# RTC.net
KiCad netlist of a schematic drawn in Altium Designer
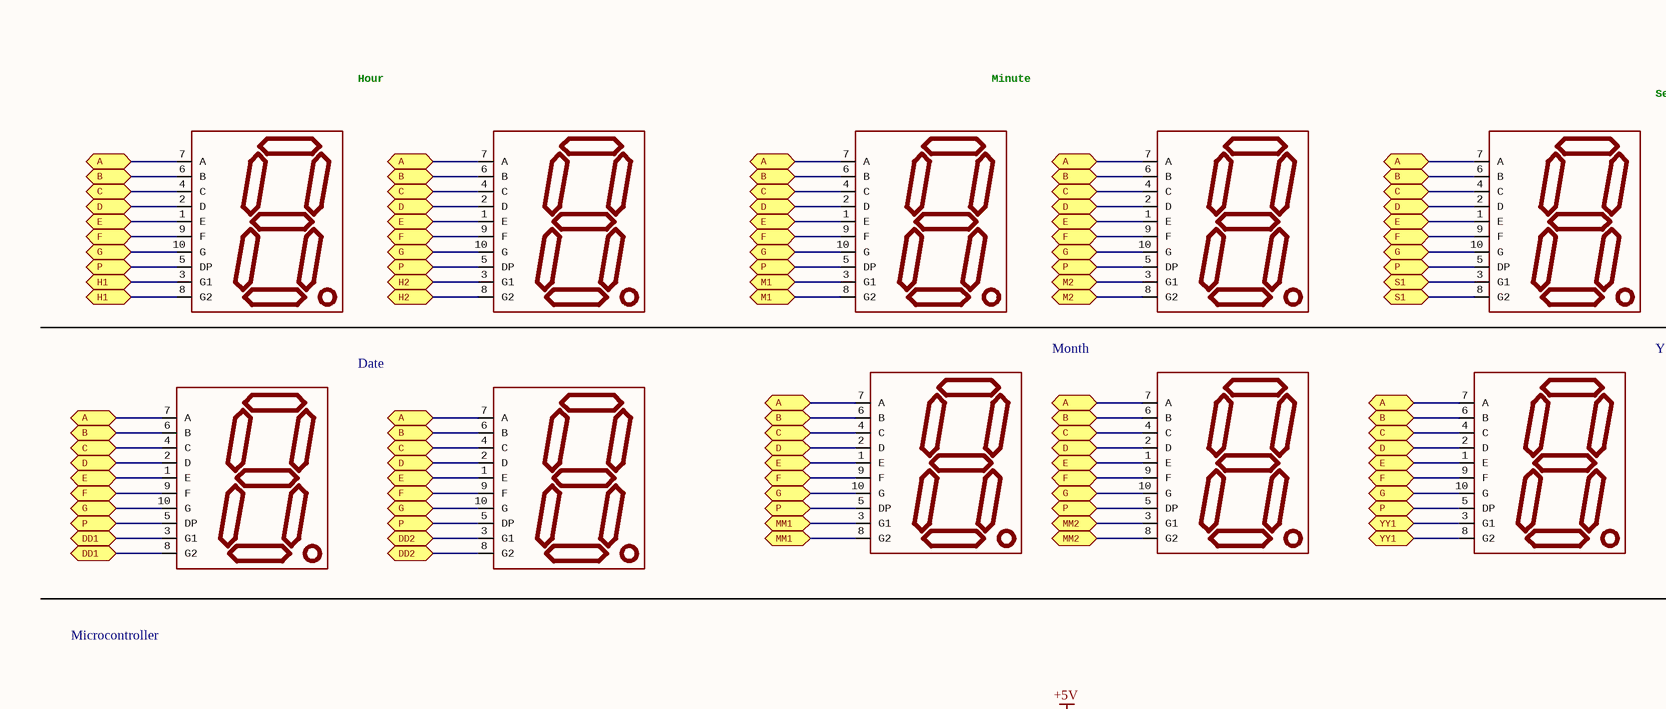
[diagram p0: RTC.SchDoc, top left]
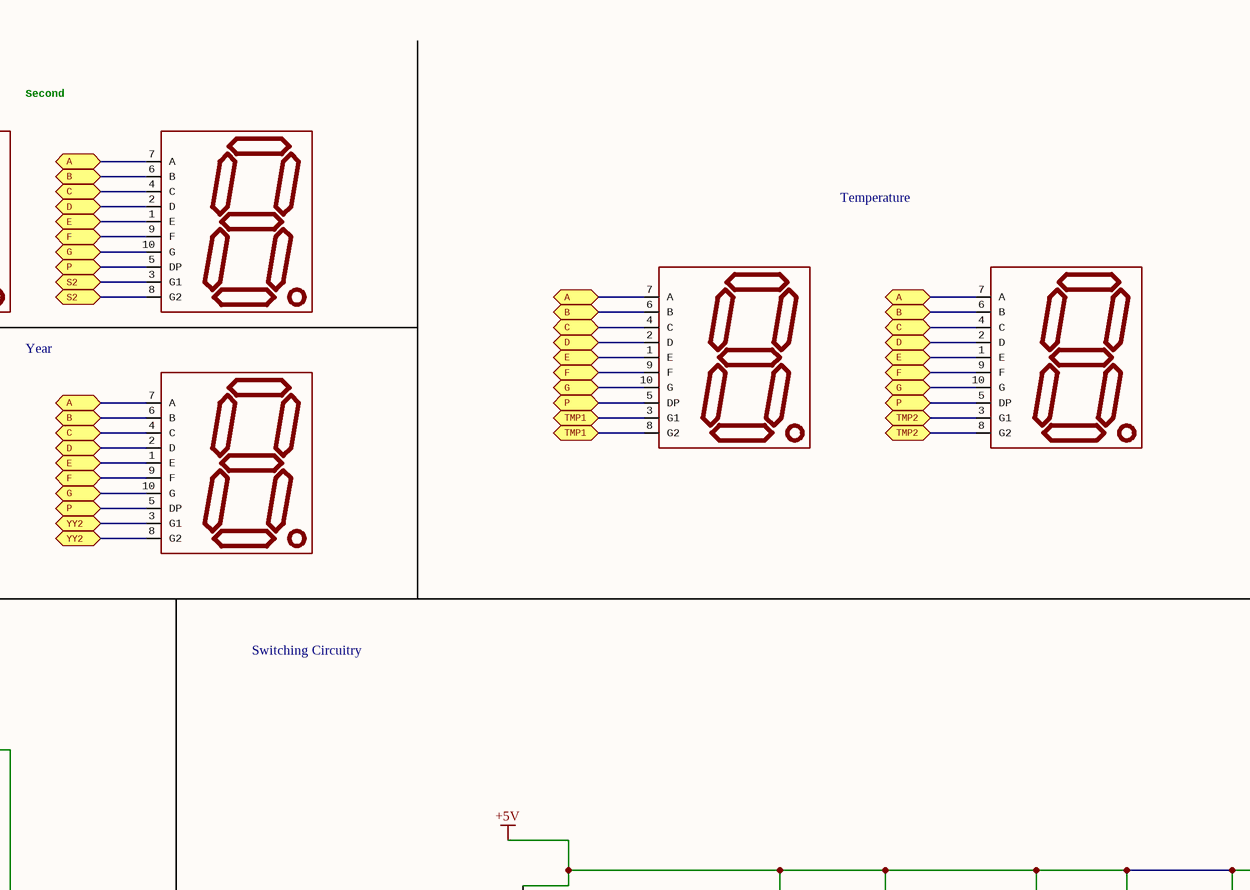
[diagram p1: RTC.SchDoc, top right]
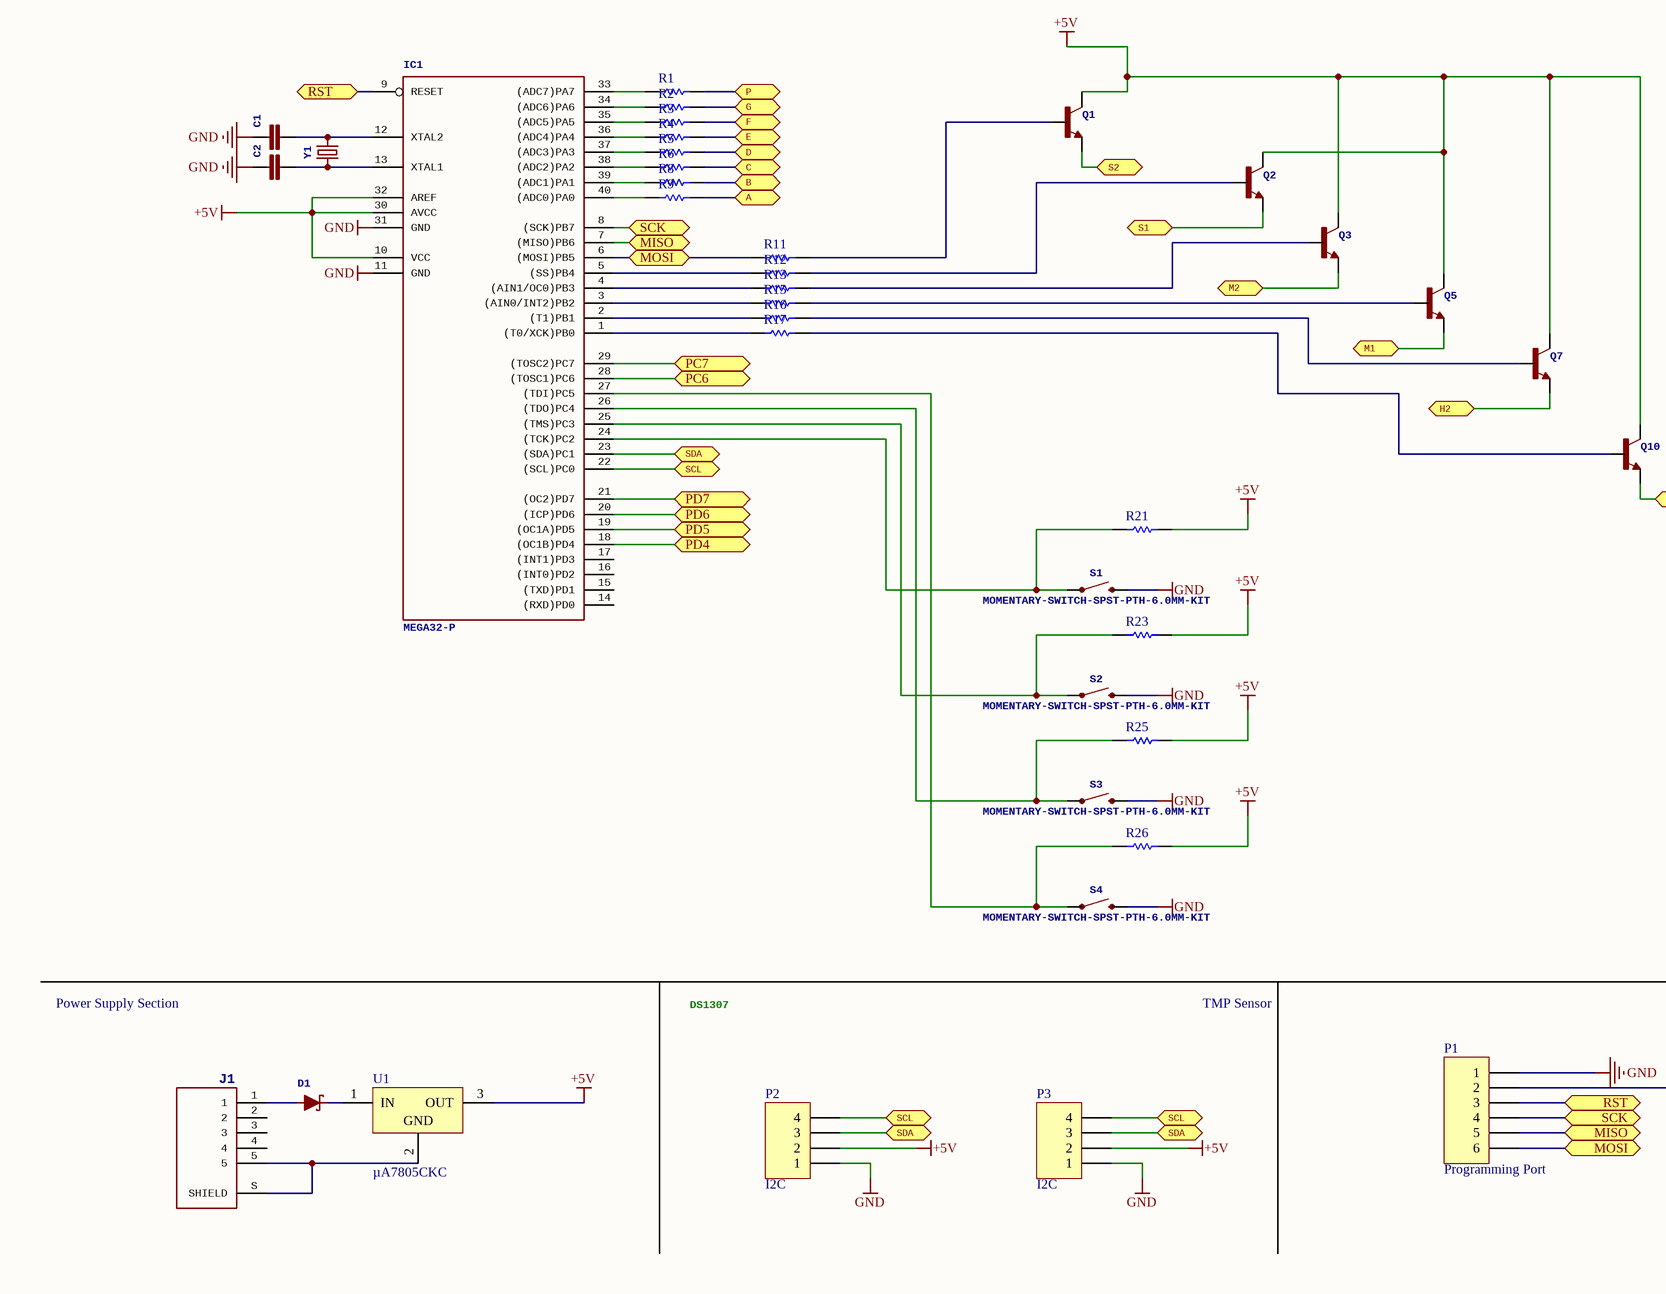
[diagram p2: RTC.SchDoc, bottom left]
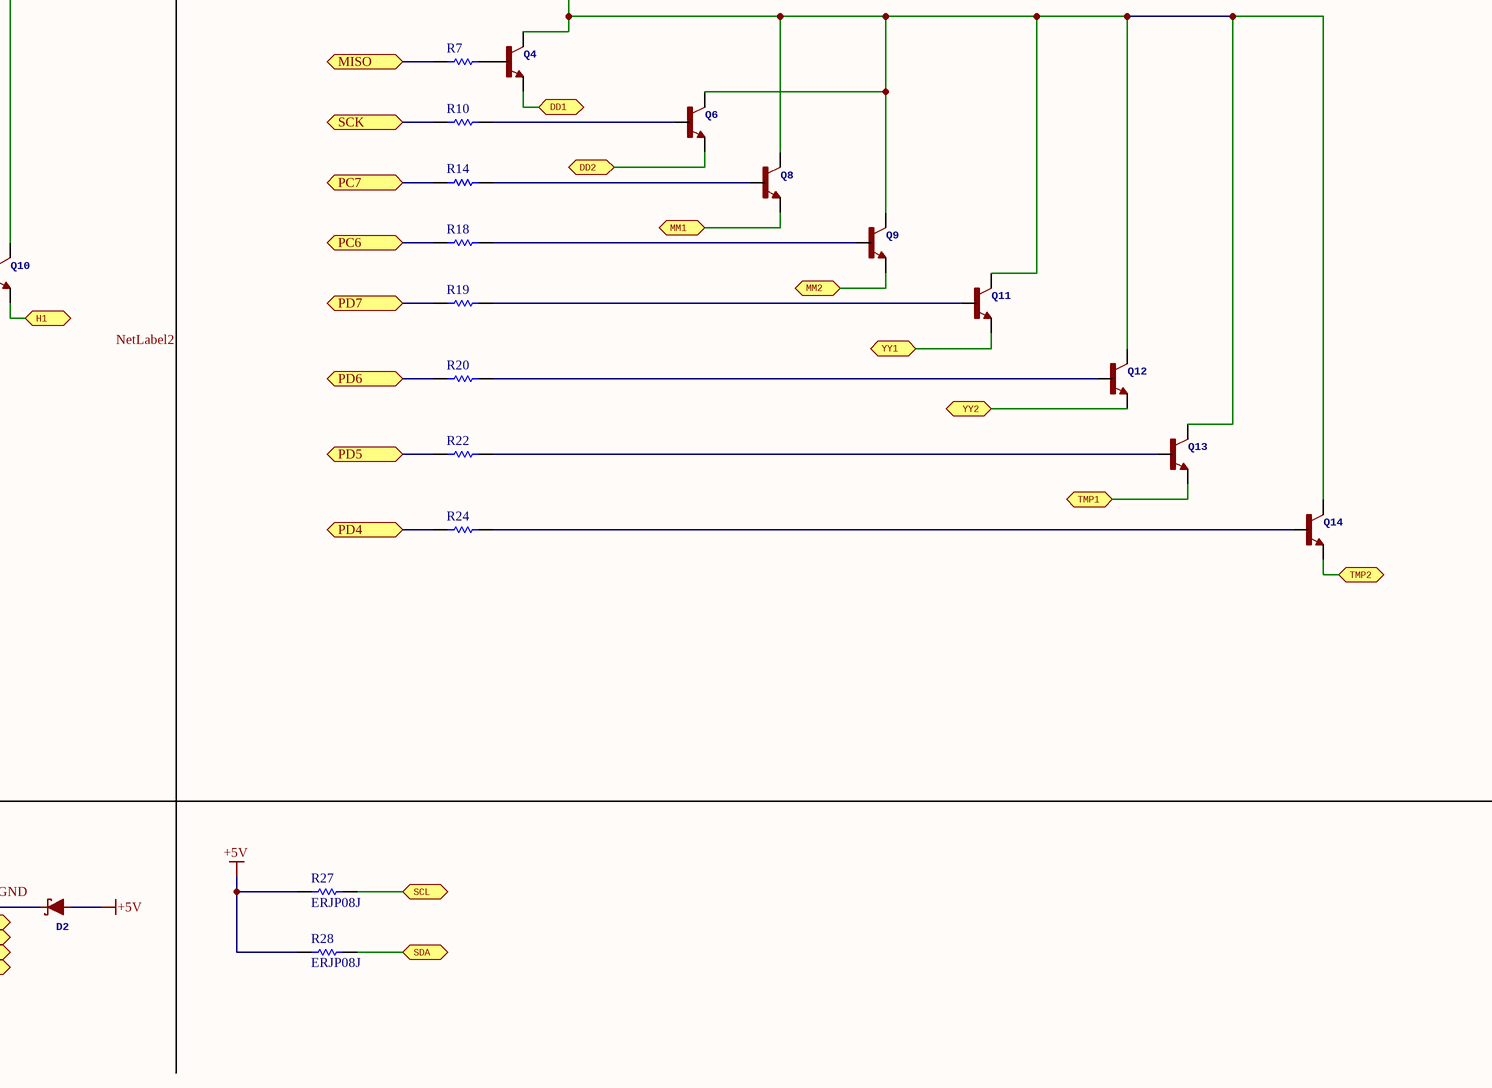
[diagram p3: RTC.SchDoc, bottom right]

(export (version "E")
  (design (tool "Eeschema 10.0.6"))
  (components
    (comp (ref "1")
      (value "7-SEGMENT-DISPLAYPTH")
      (footprint "7-SEGMENT-DISPLAY")
      (libsource (lib "SparkFun-Retired") (part "7-SEGMENT-DISPLAYPTH"))
    )
    (comp (ref "2")
      (value "7-SEGMENT-DISPLAYPTH")
      (footprint "7-SEGMENT-DISPLAY")
      (libsource (lib "SparkFun-Retired") (part "7-SEGMENT-DISPLAYPTH"))
    )
    (comp (ref "3")
      (value "7-SEGMENT-DISPLAYPTH")
      (footprint "7-SEGMENT-DISPLAY")
      (libsource (lib "SparkFun-Retired") (part "7-SEGMENT-DISPLAYPTH"))
    )
    (comp (ref "4")
      (value "7-SEGMENT-DISPLAYPTH")
      (footprint "7-SEGMENT-DISPLAY")
      (libsource (lib "SparkFun-Retired") (part "7-SEGMENT-DISPLAYPTH"))
    )
    (comp (ref "5")
      (value "7-SEGMENT-DISPLAYPTH")
      (footprint "7-SEGMENT-DISPLAY")
      (libsource (lib "SparkFun-Retired") (part "7-SEGMENT-DISPLAYPTH"))
    )
    (comp (ref "6")
      (value "7-SEGMENT-DISPLAYPTH")
      (footprint "7-SEGMENT-DISPLAY")
      (libsource (lib "SparkFun-Retired") (part "7-SEGMENT-DISPLAYPTH"))
    )
    (comp (ref "7")
      (value "7-SEGMENT-DISPLAYPTH")
      (footprint "7-SEGMENT-DISPLAY")
      (libsource (lib "SparkFun-Retired") (part "7-SEGMENT-DISPLAYPTH"))
    )
    (comp (ref "8")
      (value "7-SEGMENT-DISPLAYPTH")
      (footprint "7-SEGMENT-DISPLAY")
      (libsource (lib "SparkFun-Retired") (part "7-SEGMENT-DISPLAYPTH"))
    )
    (comp (ref "9")
      (value "7-SEGMENT-DISPLAYPTH")
      (footprint "7-SEGMENT-DISPLAY")
      (libsource (lib "SparkFun-Retired") (part "7-SEGMENT-DISPLAYPTH"))
    )
    (comp (ref "10")
      (value "7-SEGMENT-DISPLAYPTH")
      (footprint "7-SEGMENT-DISPLAY")
      (libsource (lib "SparkFun-Retired") (part "7-SEGMENT-DISPLAYPTH"))
    )
    (comp (ref "11")
      (value "7-SEGMENT-DISPLAYPTH")
      (footprint "7-SEGMENT-DISPLAY")
      (libsource (lib "SparkFun-Retired") (part "7-SEGMENT-DISPLAYPTH"))
    )
    (comp (ref "12")
      (value "7-SEGMENT-DISPLAYPTH")
      (footprint "7-SEGMENT-DISPLAY")
      (libsource (lib "SparkFun-Retired") (part "7-SEGMENT-DISPLAYPTH"))
    )
    (comp (ref "13")
      (value "7-SEGMENT-DISPLAYPTH")
      (footprint "7-SEGMENT-DISPLAY")
      (libsource (lib "SparkFun-Retired") (part "7-SEGMENT-DISPLAYPTH"))
    )
    (comp (ref "14")
      (value "7-SEGMENT-DISPLAYPTH")
      (footprint "7-SEGMENT-DISPLAY")
      (libsource (lib "SparkFun-Retired") (part "7-SEGMENT-DISPLAYPTH"))
    )
    (comp (ref "C1")
      (value "22PF-PTH-2.54MM-200V-5%")
      (footprint "CAP-PTH-2.54")
      (libsource (lib "SparkFun-Capacitors") (part "22PF-PTH-2.54MM-200V-5%"))
    )
    (comp (ref "C2")
      (value "22PF-PTH-2.54MM-200V-5%")
      (footprint "CAP-PTH-2.54")
      (libsource (lib "SparkFun-Capacitors") (part "22PF-PTH-2.54MM-200V-5%"))
    )
    (comp (ref "D1")
      (value "Schottky diode    A Schottky diode is a semiconductor diode which has a low forward voltage drop and a very fast switching action.")
      (footprint "SMA-DIODE")
      (libsource (lib "SparkFun-DiscreteSemi") (part "DIODE-SCHOTTKY-SS14"))
    )
    (comp (ref "D2")
      (value "Schottky diode    A Schottky diode is a semiconductor diode which has a low forward voltage drop and a very fast switching action.")
      (footprint "SMA-DIODE")
      (libsource (lib "SparkFun-DiscreteSemi") (part "DIODE-SCHOTTKY-SS14"))
    )
    (comp (ref "IC1")
      (value "MEGA32-P")
      (footprint "40P6")
      (fields (field (name "MPN") "ATMEGA32-16PU"))
      (libsource (lib "atmel") (part "MEGA32-P"))
    )
    (comp (ref "J1")
      (value "SMD+DIP Micro USB; MICRO-B-SMD")
      (footprint "HRS_ZX62D-B-5P8")
      (fields (field (name "MP") "ZX62D-B-5P8") (field (name "MF") "Hirose"))
      (libsource (lib "MicroUSB") (part "ZX62D-B-5P8"))
    )
    (comp (ref "P1")
      (value "Programming Port")
      (footprint "HDR1X6")
      (description "Header, 6-Pin")
      (fields (field (name "PUBLISHER") "Altium Limited"))
      (libsource (lib "Miscellaneous Connectors") (part "Header 6"))
    )
    (comp (ref "P2")
      (value "I2C")
      (footprint "HDR1X4")
      (description "Header, 4-Pin")
      (fields (field (name "PUBLISHER") "Altium Limited"))
      (libsource (lib "Miscellaneous Connectors") (part "Header 4"))
    )
    (comp (ref "P3")
      (value "I2C")
      (footprint "HDR1X4")
      (description "Header, 4-Pin")
      (fields (field (name "PUBLISHER") "Altium Limited"))
      (libsource (lib "Miscellaneous Connectors") (part "Header 4"))
    )
    (comp (ref "Q1")
      (value "NPN transistor    Current controlled devices typically used to amplify current or used as a switch.         BC547 -     COM-08928    (TO-92 45V 100mA) (1.Collector 2.Base 3.Emitter)             2N3904 -     COM-00521    (TO-92 40V 200mA) (1.Emitter 2.Base 3.Collector)             P2N2222A -     COM-12852    (TO-92 40V 600mA) (1.Collector 2.Base 3.Emitter)")
      (footprint "SOT23-3")
      (libsource (lib "SparkFun-DiscreteSemi") (part "TRANS_NPN-MMBT2222AL"))
    )
    (comp (ref "Q2")
      (value "NPN transistor    Current controlled devices typically used to amplify current or used as a switch.         BC547 -     COM-08928    (TO-92 45V 100mA) (1.Collector 2.Base 3.Emitter)             2N3904 -     COM-00521    (TO-92 40V 200mA) (1.Emitter 2.Base 3.Collector)             P2N2222A -     COM-12852    (TO-92 40V 600mA) (1.Collector 2.Base 3.Emitter)")
      (footprint "SOT23-3")
      (libsource (lib "SparkFun-DiscreteSemi") (part "TRANS_NPN-MMBT2222AL"))
    )
    (comp (ref "Q3")
      (value "NPN transistor    Current controlled devices typically used to amplify current or used as a switch.         BC547 -     COM-08928    (TO-92 45V 100mA) (1.Collector 2.Base 3.Emitter)             2N3904 -     COM-00521    (TO-92 40V 200mA) (1.Emitter 2.Base 3.Collector)             P2N2222A -     COM-12852    (TO-92 40V 600mA) (1.Collector 2.Base 3.Emitter)")
      (footprint "SOT23-3")
      (libsource (lib "SparkFun-DiscreteSemi") (part "TRANS_NPN-MMBT2222AL"))
    )
    (comp (ref "Q4")
      (value "NPN transistor    Current controlled devices typically used to amplify current or used as a switch.         BC547 -     COM-08928    (TO-92 45V 100mA) (1.Collector 2.Base 3.Emitter)             2N3904 -     COM-00521    (TO-92 40V 200mA) (1.Emitter 2.Base 3.Collector)             P2N2222A -     COM-12852    (TO-92 40V 600mA) (1.Collector 2.Base 3.Emitter)")
      (footprint "SOT23-3")
      (libsource (lib "SparkFun-DiscreteSemi") (part "TRANS_NPN-MMBT2222AL"))
    )
    (comp (ref "Q5")
      (value "NPN transistor    Current controlled devices typically used to amplify current or used as a switch.         BC547 -     COM-08928    (TO-92 45V 100mA) (1.Collector 2.Base 3.Emitter)             2N3904 -     COM-00521    (TO-92 40V 200mA) (1.Emitter 2.Base 3.Collector)             P2N2222A -     COM-12852    (TO-92 40V 600mA) (1.Collector 2.Base 3.Emitter)")
      (footprint "SOT23-3")
      (libsource (lib "SparkFun-DiscreteSemi") (part "TRANS_NPN-MMBT2222AL"))
    )
    (comp (ref "Q6")
      (value "NPN transistor    Current controlled devices typically used to amplify current or used as a switch.         BC547 -     COM-08928    (TO-92 45V 100mA) (1.Collector 2.Base 3.Emitter)             2N3904 -     COM-00521    (TO-92 40V 200mA) (1.Emitter 2.Base 3.Collector)             P2N2222A -     COM-12852    (TO-92 40V 600mA) (1.Collector 2.Base 3.Emitter)")
      (footprint "SOT23-3")
      (libsource (lib "SparkFun-DiscreteSemi") (part "TRANS_NPN-MMBT2222AL"))
    )
    (comp (ref "Q7")
      (value "NPN transistor    Current controlled devices typically used to amplify current or used as a switch.         BC547 -     COM-08928    (TO-92 45V 100mA) (1.Collector 2.Base 3.Emitter)             2N3904 -     COM-00521    (TO-92 40V 200mA) (1.Emitter 2.Base 3.Collector)             P2N2222A -     COM-12852    (TO-92 40V 600mA) (1.Collector 2.Base 3.Emitter)")
      (footprint "SOT23-3")
      (libsource (lib "SparkFun-DiscreteSemi") (part "TRANS_NPN-MMBT2222AL"))
    )
    (comp (ref "Q8")
      (value "NPN transistor    Current controlled devices typically used to amplify current or used as a switch.         BC547 -     COM-08928    (TO-92 45V 100mA) (1.Collector 2.Base 3.Emitter)             2N3904 -     COM-00521    (TO-92 40V 200mA) (1.Emitter 2.Base 3.Collector)             P2N2222A -     COM-12852    (TO-92 40V 600mA) (1.Collector 2.Base 3.Emitter)")
      (footprint "SOT23-3")
      (libsource (lib "SparkFun-DiscreteSemi") (part "TRANS_NPN-MMBT2222AL"))
    )
    (comp (ref "Q9")
      (value "NPN transistor    Current controlled devices typically used to amplify current or used as a switch.         BC547 -     COM-08928    (TO-92 45V 100mA) (1.Collector 2.Base 3.Emitter)             2N3904 -     COM-00521    (TO-92 40V 200mA) (1.Emitter 2.Base 3.Collector)             P2N2222A -     COM-12852    (TO-92 40V 600mA) (1.Collector 2.Base 3.Emitter)")
      (footprint "SOT23-3")
      (libsource (lib "SparkFun-DiscreteSemi") (part "TRANS_NPN-MMBT2222AL"))
    )
    (comp (ref "Q10")
      (value "NPN transistor    Current controlled devices typically used to amplify current or used as a switch.         BC547 -     COM-08928    (TO-92 45V 100mA) (1.Collector 2.Base 3.Emitter)             2N3904 -     COM-00521    (TO-92 40V 200mA) (1.Emitter 2.Base 3.Collector)             P2N2222A -     COM-12852    (TO-92 40V 600mA) (1.Collector 2.Base 3.Emitter)")
      (footprint "SOT23-3")
      (libsource (lib "SparkFun-DiscreteSemi") (part "TRANS_NPN-MMBT2222AL"))
    )
    (comp (ref "Q11")
      (value "NPN transistor    Current controlled devices typically used to amplify current or used as a switch.         BC547 -     COM-08928    (TO-92 45V 100mA) (1.Collector 2.Base 3.Emitter)             2N3904 -     COM-00521    (TO-92 40V 200mA) (1.Emitter 2.Base 3.Collector)             P2N2222A -     COM-12852    (TO-92 40V 600mA) (1.Collector 2.Base 3.Emitter)")
      (footprint "SOT23-3")
      (libsource (lib "SparkFun-DiscreteSemi") (part "TRANS_NPN-MMBT2222AL"))
    )
    (comp (ref "Q12")
      (value "NPN transistor    Current controlled devices typically used to amplify current or used as a switch.         BC547 -     COM-08928    (TO-92 45V 100mA) (1.Collector 2.Base 3.Emitter)             2N3904 -     COM-00521    (TO-92 40V 200mA) (1.Emitter 2.Base 3.Collector)             P2N2222A -     COM-12852    (TO-92 40V 600mA) (1.Collector 2.Base 3.Emitter)")
      (footprint "SOT23-3")
      (libsource (lib "SparkFun-DiscreteSemi") (part "TRANS_NPN-MMBT2222AL"))
    )
    (comp (ref "Q13")
      (value "NPN transistor    Current controlled devices typically used to amplify current or used as a switch.         BC547 -     COM-08928    (TO-92 45V 100mA) (1.Collector 2.Base 3.Emitter)             2N3904 -     COM-00521    (TO-92 40V 200mA) (1.Emitter 2.Base 3.Collector)             P2N2222A -     COM-12852    (TO-92 40V 600mA) (1.Collector 2.Base 3.Emitter)")
      (footprint "SOT23-3")
      (libsource (lib "SparkFun-DiscreteSemi") (part "TRANS_NPN-MMBT2222AL"))
    )
    (comp (ref "Q14")
      (value "NPN transistor    Current controlled devices typically used to amplify current or used as a switch.         BC547 -     COM-08928    (TO-92 45V 100mA) (1.Collector 2.Base 3.Emitter)             2N3904 -     COM-00521    (TO-92 40V 200mA) (1.Emitter 2.Base 3.Collector)             P2N2222A -     COM-12852    (TO-92 40V 600mA) (1.Collector 2.Base 3.Emitter)")
      (footprint "SOT23-3")
      (libsource (lib "SparkFun-DiscreteSemi") (part "TRANS_NPN-MMBT2222AL"))
    )
    (comp (ref "R1")
      (value "~")
      (footprint "8-1206")
      (description "Anti-Surge Thick Film Chip Resistor, 10 Ohm to 1M Ohm Range, 5% Tolerance, 1206 Size, 0.25 W")
      (fields (field (name "PUBLISHER") "Altium Limited"))
      (libsource (lib "Panasonic Resistor") (part "ERJP08J"))
    )
    (comp (ref "R2")
      (value "~")
      (footprint "8-1206")
      (description "Anti-Surge Thick Film Chip Resistor, 10 Ohm to 1M Ohm Range, 5% Tolerance, 1206 Size, 0.25 W")
      (fields (field (name "PUBLISHER") "Altium Limited"))
      (libsource (lib "Panasonic Resistor") (part "ERJP08J"))
    )
    (comp (ref "R3")
      (value "~")
      (footprint "8-1206")
      (description "Anti-Surge Thick Film Chip Resistor, 10 Ohm to 1M Ohm Range, 5% Tolerance, 1206 Size, 0.25 W")
      (fields (field (name "PUBLISHER") "Altium Limited"))
      (libsource (lib "Panasonic Resistor") (part "ERJP08J"))
    )
    (comp (ref "R4")
      (value "~")
      (footprint "8-1206")
      (description "Anti-Surge Thick Film Chip Resistor, 10 Ohm to 1M Ohm Range, 5% Tolerance, 1206 Size, 0.25 W")
      (fields (field (name "PUBLISHER") "Altium Limited"))
      (libsource (lib "Panasonic Resistor") (part "ERJP08J"))
    )
    (comp (ref "R5")
      (value "~")
      (footprint "8-1206")
      (description "Anti-Surge Thick Film Chip Resistor, 10 Ohm to 1M Ohm Range, 5% Tolerance, 1206 Size, 0.25 W")
      (fields (field (name "PUBLISHER") "Altium Limited"))
      (libsource (lib "Panasonic Resistor") (part "ERJP08J"))
    )
    (comp (ref "R6")
      (value "~")
      (footprint "8-1206")
      (description "Anti-Surge Thick Film Chip Resistor, 10 Ohm to 1M Ohm Range, 5% Tolerance, 1206 Size, 0.25 W")
      (fields (field (name "PUBLISHER") "Altium Limited"))
      (libsource (lib "Panasonic Resistor") (part "ERJP08J"))
    )
    (comp (ref "R7")
      (value "~")
      (footprint "8-1206")
      (description "Anti-Surge Thick Film Chip Resistor, 10 Ohm to 1M Ohm Range, 5% Tolerance, 1206 Size, 0.25 W")
      (fields (field (name "PUBLISHER") "Altium Limited"))
      (libsource (lib "Panasonic Resistor") (part "ERJP08J"))
    )
    (comp (ref "R8")
      (value "~")
      (footprint "8-1206")
      (description "Anti-Surge Thick Film Chip Resistor, 10 Ohm to 1M Ohm Range, 5% Tolerance, 1206 Size, 0.25 W")
      (fields (field (name "PUBLISHER") "Altium Limited"))
      (libsource (lib "Panasonic Resistor") (part "ERJP08J"))
    )
    (comp (ref "R9")
      (value "~")
      (footprint "8-1206")
      (description "Anti-Surge Thick Film Chip Resistor, 10 Ohm to 1M Ohm Range, 5% Tolerance, 1206 Size, 0.25 W")
      (fields (field (name "PUBLISHER") "Altium Limited"))
      (libsource (lib "Panasonic Resistor") (part "ERJP08J"))
    )
    (comp (ref "R10")
      (value "~")
      (footprint "8-1206")
      (description "Anti-Surge Thick Film Chip Resistor, 10 Ohm to 1M Ohm Range, 5% Tolerance, 1206 Size, 0.25 W")
      (fields (field (name "PUBLISHER") "Altium Limited"))
      (libsource (lib "Panasonic Resistor") (part "ERJP08J"))
    )
    (comp (ref "R11")
      (value "~")
      (footprint "8-1206")
      (description "Anti-Surge Thick Film Chip Resistor, 10 Ohm to 1M Ohm Range, 5% Tolerance, 1206 Size, 0.25 W")
      (fields (field (name "PUBLISHER") "Altium Limited"))
      (libsource (lib "Panasonic Resistor") (part "ERJP08J"))
    )
    (comp (ref "R12")
      (value "~")
      (footprint "8-1206")
      (description "Anti-Surge Thick Film Chip Resistor, 10 Ohm to 1M Ohm Range, 5% Tolerance, 1206 Size, 0.25 W")
      (fields (field (name "PUBLISHER") "Altium Limited"))
      (libsource (lib "Panasonic Resistor") (part "ERJP08J"))
    )
    (comp (ref "R13")
      (value "~")
      (footprint "8-1206")
      (description "Anti-Surge Thick Film Chip Resistor, 10 Ohm to 1M Ohm Range, 5% Tolerance, 1206 Size, 0.25 W")
      (fields (field (name "PUBLISHER") "Altium Limited"))
      (libsource (lib "Panasonic Resistor") (part "ERJP08J"))
    )
    (comp (ref "R14")
      (value "~")
      (footprint "8-1206")
      (description "Anti-Surge Thick Film Chip Resistor, 10 Ohm to 1M Ohm Range, 5% Tolerance, 1206 Size, 0.25 W")
      (fields (field (name "PUBLISHER") "Altium Limited"))
      (libsource (lib "Panasonic Resistor") (part "ERJP08J"))
    )
    (comp (ref "R15")
      (value "~")
      (footprint "8-1206")
      (description "Anti-Surge Thick Film Chip Resistor, 10 Ohm to 1M Ohm Range, 5% Tolerance, 1206 Size, 0.25 W")
      (fields (field (name "PUBLISHER") "Altium Limited"))
      (libsource (lib "Panasonic Resistor") (part "ERJP08J"))
    )
    (comp (ref "R16")
      (value "~")
      (footprint "8-1206")
      (description "Anti-Surge Thick Film Chip Resistor, 10 Ohm to 1M Ohm Range, 5% Tolerance, 1206 Size, 0.25 W")
      (fields (field (name "PUBLISHER") "Altium Limited"))
      (libsource (lib "Panasonic Resistor") (part "ERJP08J"))
    )
    (comp (ref "R17")
      (value "~")
      (footprint "8-1206")
      (description "Anti-Surge Thick Film Chip Resistor, 10 Ohm to 1M Ohm Range, 5% Tolerance, 1206 Size, 0.25 W")
      (fields (field (name "PUBLISHER") "Altium Limited"))
      (libsource (lib "Panasonic Resistor") (part "ERJP08J"))
    )
    (comp (ref "R18")
      (value "~")
      (footprint "8-1206")
      (description "Anti-Surge Thick Film Chip Resistor, 10 Ohm to 1M Ohm Range, 5% Tolerance, 1206 Size, 0.25 W")
      (fields (field (name "PUBLISHER") "Altium Limited"))
      (libsource (lib "Panasonic Resistor") (part "ERJP08J"))
    )
    (comp (ref "R19")
      (value "~")
      (footprint "8-1206")
      (description "Anti-Surge Thick Film Chip Resistor, 10 Ohm to 1M Ohm Range, 5% Tolerance, 1206 Size, 0.25 W")
      (fields (field (name "PUBLISHER") "Altium Limited"))
      (libsource (lib "Panasonic Resistor") (part "ERJP08J"))
    )
    (comp (ref "R20")
      (value "~")
      (footprint "8-1206")
      (description "Anti-Surge Thick Film Chip Resistor, 10 Ohm to 1M Ohm Range, 5% Tolerance, 1206 Size, 0.25 W")
      (fields (field (name "PUBLISHER") "Altium Limited"))
      (libsource (lib "Panasonic Resistor") (part "ERJP08J"))
    )
    (comp (ref "R21")
      (value "~")
      (footprint "8-1206")
      (description "Anti-Surge Thick Film Chip Resistor, 10 Ohm to 1M Ohm Range, 5% Tolerance, 1206 Size, 0.25 W")
      (fields (field (name "PUBLISHER") "Altium Limited"))
      (libsource (lib "Panasonic Resistor") (part "ERJP08J"))
    )
    (comp (ref "R22")
      (value "~")
      (footprint "8-1206")
      (description "Anti-Surge Thick Film Chip Resistor, 10 Ohm to 1M Ohm Range, 5% Tolerance, 1206 Size, 0.25 W")
      (fields (field (name "PUBLISHER") "Altium Limited"))
      (libsource (lib "Panasonic Resistor") (part "ERJP08J"))
    )
    (comp (ref "R23")
      (value "~")
      (footprint "8-1206")
      (description "Anti-Surge Thick Film Chip Resistor, 10 Ohm to 1M Ohm Range, 5% Tolerance, 1206 Size, 0.25 W")
      (fields (field (name "PUBLISHER") "Altium Limited"))
      (libsource (lib "Panasonic Resistor") (part "ERJP08J"))
    )
    (comp (ref "R24")
      (value "~")
      (footprint "8-1206")
      (description "Anti-Surge Thick Film Chip Resistor, 10 Ohm to 1M Ohm Range, 5% Tolerance, 1206 Size, 0.25 W")
      (fields (field (name "PUBLISHER") "Altium Limited"))
      (libsource (lib "Panasonic Resistor") (part "ERJP08J"))
    )
    (comp (ref "R25")
      (value "~")
      (footprint "8-1206")
      (description "Anti-Surge Thick Film Chip Resistor, 10 Ohm to 1M Ohm Range, 5% Tolerance, 1206 Size, 0.25 W")
      (fields (field (name "PUBLISHER") "Altium Limited"))
      (libsource (lib "Panasonic Resistor") (part "ERJP08J"))
    )
    (comp (ref "R26")
      (value "~")
      (footprint "8-1206")
      (description "Anti-Surge Thick Film Chip Resistor, 10 Ohm to 1M Ohm Range, 5% Tolerance, 1206 Size, 0.25 W")
      (fields (field (name "PUBLISHER") "Altium Limited"))
      (libsource (lib "Panasonic Resistor") (part "ERJP08J"))
    )
    (comp (ref "R27")
      (value "ERJP08J")
      (footprint "8-1206")
      (description "Anti-Surge Thick Film Chip Resistor, 10 Ohm to 1M Ohm Range, 5% Tolerance, 1206 Size, 0.25 W")
      (fields (field (name "PUBLISHER") "Altium Limited"))
      (libsource (lib "Panasonic Resistor") (part "ERJP08J"))
    )
    (comp (ref "R28")
      (value "ERJP08J")
      (footprint "8-1206")
      (description "Anti-Surge Thick Film Chip Resistor, 10 Ohm to 1M Ohm Range, 5% Tolerance, 1206 Size, 0.25 W")
      (fields (field (name "PUBLISHER") "Altium Limited"))
      (libsource (lib "Panasonic Resistor") (part "ERJP08J"))
    )
    (comp (ref "S1")
      (value "MOMENTARY-SWITCH-SPST-PTH-6.0MM-KIT")
      (footprint "TACTILE_SWITCH_PTH_6.0MM_KIT")
      (libsource (lib "SparkFun-Switches") (part "MOMENTARY-SWITCH-SPST-PTH-6.0MM-KIT"))
    )
    (comp (ref "S2")
      (value "MOMENTARY-SWITCH-SPST-PTH-6.0MM-KIT")
      (footprint "TACTILE_SWITCH_PTH_6.0MM_KIT")
      (libsource (lib "SparkFun-Switches") (part "MOMENTARY-SWITCH-SPST-PTH-6.0MM-KIT"))
    )
    (comp (ref "S3")
      (value "MOMENTARY-SWITCH-SPST-PTH-6.0MM-KIT")
      (footprint "TACTILE_SWITCH_PTH_6.0MM_KIT")
      (libsource (lib "SparkFun-Switches") (part "MOMENTARY-SWITCH-SPST-PTH-6.0MM-KIT"))
    )
    (comp (ref "S4")
      (value "MOMENTARY-SWITCH-SPST-PTH-6.0MM-KIT")
      (footprint "TACTILE_SWITCH_PTH_6.0MM_KIT")
      (libsource (lib "SparkFun-Switches") (part "MOMENTARY-SWITCH-SPST-PTH-6.0MM-KIT"))
    )
    (comp (ref "U1")
      (value "µA7805CKC")
      (footprint "KC03")
      (description "Positive-Voltage Regulator")
      (fields (field (name "PUBLISHER") "Altium Limited"))
      (libsource (lib "TI Power Mgt Voltage Regulator") (part "µA7805CKC"))
    )
    (comp (ref "Y1")
      (value "CRYSTAL-16MHZPTH-HC49US")
      (footprint "HC49US")
      (libsource (lib "SparkFun-Clocks") (part "CRYSTAL-16MHZPTH-HC49US"))
    )
  )
  (nets
    (net (code "1") (name "+5V") (class "Default")
      (node (ref "D2") (pin "A") (pinfunction "A_A") (pintype "passive"))
      (node (ref "IC1") (pin "10") (pinfunction "VCC_10") (pintype "power_in"))
      (node (ref "IC1") (pin "30") (pinfunction "AVCC_30") (pintype "power_in"))
      (node (ref "IC1") (pin "32") (pinfunction "AREF_32") (pintype "passive"))
      (node (ref "P2") (pin "2") (pinfunction "2_2") (pintype "passive"))
      (node (ref "P3") (pin "2") (pinfunction "2_2") (pintype "passive"))
      (node (ref "Q1") (pin "3") (pinfunction "C_3") (pintype "passive"))
      (node (ref "Q10") (pin "3") (pinfunction "C_3") (pintype "passive"))
      (node (ref "Q11") (pin "3") (pinfunction "C_3") (pintype "passive"))
      (node (ref "Q12") (pin "3") (pinfunction "C_3") (pintype "passive"))
      (node (ref "Q13") (pin "3") (pinfunction "C_3") (pintype "passive"))
      (node (ref "Q14") (pin "3") (pinfunction "C_3") (pintype "passive"))
      (node (ref "Q2") (pin "3") (pinfunction "C_3") (pintype "passive"))
      (node (ref "Q3") (pin "3") (pinfunction "C_3") (pintype "passive"))
      (node (ref "Q4") (pin "3") (pinfunction "C_3") (pintype "passive"))
      (node (ref "Q5") (pin "3") (pinfunction "C_3") (pintype "passive"))
      (node (ref "Q6") (pin "3") (pinfunction "C_3") (pintype "passive"))
      (node (ref "Q7") (pin "3") (pinfunction "C_3") (pintype "passive"))
      (node (ref "Q8") (pin "3") (pinfunction "C_3") (pintype "passive"))
      (node (ref "Q9") (pin "3") (pinfunction "C_3") (pintype "passive"))
      (node (ref "R21") (pin "2") (pinfunction "2_2") (pintype "passive"))
      (node (ref "R23") (pin "2") (pinfunction "2_2") (pintype "passive"))
      (node (ref "R25") (pin "2") (pinfunction "2_2") (pintype "passive"))
      (node (ref "R26") (pin "2") (pinfunction "2_2") (pintype "passive"))
      (node (ref "R27") (pin "1") (pinfunction "1_1") (pintype "passive"))
      (node (ref "R28") (pin "1") (pinfunction "1_1") (pintype "passive"))
      (node (ref "U1") (pin "3") (pinfunction "OUT_3") (pintype "power_in"))
    )
    (net (code "2") (name "/A") (class "Default")
      (node (ref "1") (pin "7") (pinfunction "A_7") (pintype "passive"))
      (node (ref "10") (pin "7") (pinfunction "A_7") (pintype "passive"))
      (node (ref "11") (pin "7") (pinfunction "A_7") (pintype "passive"))
      (node (ref "12") (pin "7") (pinfunction "A_7") (pintype "passive"))
      (node (ref "13") (pin "7") (pinfunction "A_7") (pintype "passive"))
      (node (ref "14") (pin "7") (pinfunction "A_7") (pintype "passive"))
      (node (ref "2") (pin "7") (pinfunction "A_7") (pintype "passive"))
      (node (ref "3") (pin "7") (pinfunction "A_7") (pintype "passive"))
      (node (ref "4") (pin "7") (pinfunction "A_7") (pintype "passive"))
      (node (ref "5") (pin "7") (pinfunction "A_7") (pintype "passive"))
      (node (ref "6") (pin "7") (pinfunction "A_7") (pintype "passive"))
      (node (ref "7") (pin "7") (pinfunction "A_7") (pintype "passive"))
      (node (ref "8") (pin "7") (pinfunction "A_7") (pintype "passive"))
      (node (ref "9") (pin "7") (pinfunction "A_7") (pintype "passive"))
      (node (ref "R9") (pin "2") (pinfunction "2_2") (pintype "passive"))
    )
    (net (code "3") (name "/B") (class "Default")
      (node (ref "1") (pin "6") (pinfunction "B_6") (pintype "passive"))
      (node (ref "10") (pin "6") (pinfunction "B_6") (pintype "passive"))
      (node (ref "11") (pin "6") (pinfunction "B_6") (pintype "passive"))
      (node (ref "12") (pin "6") (pinfunction "B_6") (pintype "passive"))
      (node (ref "13") (pin "6") (pinfunction "B_6") (pintype "passive"))
      (node (ref "14") (pin "6") (pinfunction "B_6") (pintype "passive"))
      (node (ref "2") (pin "6") (pinfunction "B_6") (pintype "passive"))
      (node (ref "3") (pin "6") (pinfunction "B_6") (pintype "passive"))
      (node (ref "4") (pin "6") (pinfunction "B_6") (pintype "passive"))
      (node (ref "5") (pin "6") (pinfunction "B_6") (pintype "passive"))
      (node (ref "6") (pin "6") (pinfunction "B_6") (pintype "passive"))
      (node (ref "7") (pin "6") (pinfunction "B_6") (pintype "passive"))
      (node (ref "8") (pin "6") (pinfunction "B_6") (pintype "passive"))
      (node (ref "9") (pin "6") (pinfunction "B_6") (pintype "passive"))
      (node (ref "R8") (pin "2") (pinfunction "2_2") (pintype "passive"))
    )
    (net (code "4") (name "/C") (class "Default")
      (node (ref "1") (pin "4") (pinfunction "C_4") (pintype "passive"))
      (node (ref "10") (pin "4") (pinfunction "C_4") (pintype "passive"))
      (node (ref "11") (pin "4") (pinfunction "C_4") (pintype "passive"))
      (node (ref "12") (pin "4") (pinfunction "C_4") (pintype "passive"))
      (node (ref "13") (pin "4") (pinfunction "C_4") (pintype "passive"))
      (node (ref "14") (pin "4") (pinfunction "C_4") (pintype "passive"))
      (node (ref "2") (pin "4") (pinfunction "C_4") (pintype "passive"))
      (node (ref "3") (pin "4") (pinfunction "C_4") (pintype "passive"))
      (node (ref "4") (pin "4") (pinfunction "C_4") (pintype "passive"))
      (node (ref "5") (pin "4") (pinfunction "C_4") (pintype "passive"))
      (node (ref "6") (pin "4") (pinfunction "C_4") (pintype "passive"))
      (node (ref "7") (pin "4") (pinfunction "C_4") (pintype "passive"))
      (node (ref "8") (pin "4") (pinfunction "C_4") (pintype "passive"))
      (node (ref "9") (pin "4") (pinfunction "C_4") (pintype "passive"))
      (node (ref "R6") (pin "2") (pinfunction "2_2") (pintype "passive"))
    )
    (net (code "5") (name "/D") (class "Default")
      (node (ref "1") (pin "2") (pinfunction "D_2") (pintype "passive"))
      (node (ref "10") (pin "2") (pinfunction "D_2") (pintype "passive"))
      (node (ref "11") (pin "2") (pinfunction "D_2") (pintype "passive"))
      (node (ref "12") (pin "2") (pinfunction "D_2") (pintype "passive"))
      (node (ref "13") (pin "2") (pinfunction "D_2") (pintype "passive"))
      (node (ref "14") (pin "2") (pinfunction "D_2") (pintype "passive"))
      (node (ref "2") (pin "2") (pinfunction "D_2") (pintype "passive"))
      (node (ref "3") (pin "2") (pinfunction "D_2") (pintype "passive"))
      (node (ref "4") (pin "2") (pinfunction "D_2") (pintype "passive"))
      (node (ref "5") (pin "2") (pinfunction "D_2") (pintype "passive"))
      (node (ref "6") (pin "2") (pinfunction "D_2") (pintype "passive"))
      (node (ref "7") (pin "2") (pinfunction "D_2") (pintype "passive"))
      (node (ref "8") (pin "2") (pinfunction "D_2") (pintype "passive"))
      (node (ref "9") (pin "2") (pinfunction "D_2") (pintype "passive"))
      (node (ref "R5") (pin "2") (pinfunction "2_2") (pintype "passive"))
    )
    (net (code "6") (name "/DD1") (class "Default")
      (node (ref "13") (pin "3") (pinfunction "G1_3") (pintype "passive"))
      (node (ref "13") (pin "8") (pinfunction "G2_8") (pintype "passive"))
      (node (ref "Q4") (pin "2") (pinfunction "E_2") (pintype "passive"))
    )
    (net (code "7") (name "/DD2") (class "Default")
      (node (ref "14") (pin "3") (pinfunction "G1_3") (pintype "passive"))
      (node (ref "14") (pin "8") (pinfunction "G2_8") (pintype "passive"))
      (node (ref "Q6") (pin "2") (pinfunction "E_2") (pintype "passive"))
    )
    (net (code "8") (name "/E") (class "Default")
      (node (ref "1") (pin "1") (pinfunction "E_1") (pintype "passive"))
      (node (ref "10") (pin "1") (pinfunction "E_1") (pintype "passive"))
      (node (ref "11") (pin "1") (pinfunction "E_1") (pintype "passive"))
      (node (ref "12") (pin "1") (pinfunction "E_1") (pintype "passive"))
      (node (ref "13") (pin "1") (pinfunction "E_1") (pintype "passive"))
      (node (ref "14") (pin "1") (pinfunction "E_1") (pintype "passive"))
      (node (ref "2") (pin "1") (pinfunction "E_1") (pintype "passive"))
      (node (ref "3") (pin "1") (pinfunction "E_1") (pintype "passive"))
      (node (ref "4") (pin "1") (pinfunction "E_1") (pintype "passive"))
      (node (ref "5") (pin "1") (pinfunction "E_1") (pintype "passive"))
      (node (ref "6") (pin "1") (pinfunction "E_1") (pintype "passive"))
      (node (ref "7") (pin "1") (pinfunction "E_1") (pintype "passive"))
      (node (ref "8") (pin "1") (pinfunction "E_1") (pintype "passive"))
      (node (ref "9") (pin "1") (pinfunction "E_1") (pintype "passive"))
      (node (ref "R4") (pin "2") (pinfunction "2_2") (pintype "passive"))
    )
    (net (code "9") (name "/F") (class "Default")
      (node (ref "1") (pin "9") (pinfunction "F_9") (pintype "passive"))
      (node (ref "10") (pin "9") (pinfunction "F_9") (pintype "passive"))
      (node (ref "11") (pin "9") (pinfunction "F_9") (pintype "passive"))
      (node (ref "12") (pin "9") (pinfunction "F_9") (pintype "passive"))
      (node (ref "13") (pin "9") (pinfunction "F_9") (pintype "passive"))
      (node (ref "14") (pin "9") (pinfunction "F_9") (pintype "passive"))
      (node (ref "2") (pin "9") (pinfunction "F_9") (pintype "passive"))
      (node (ref "3") (pin "9") (pinfunction "F_9") (pintype "passive"))
      (node (ref "4") (pin "9") (pinfunction "F_9") (pintype "passive"))
      (node (ref "5") (pin "9") (pinfunction "F_9") (pintype "passive"))
      (node (ref "6") (pin "9") (pinfunction "F_9") (pintype "passive"))
      (node (ref "7") (pin "9") (pinfunction "F_9") (pintype "passive"))
      (node (ref "8") (pin "9") (pinfunction "F_9") (pintype "passive"))
      (node (ref "9") (pin "9") (pinfunction "F_9") (pintype "passive"))
      (node (ref "R3") (pin "2") (pinfunction "2_2") (pintype "passive"))
    )
    (net (code "10") (name "/G") (class "Default")
      (node (ref "1") (pin "10") (pinfunction "G_10") (pintype "passive"))
      (node (ref "10") (pin "10") (pinfunction "G_10") (pintype "passive"))
      (node (ref "11") (pin "10") (pinfunction "G_10") (pintype "passive"))
      (node (ref "12") (pin "10") (pinfunction "G_10") (pintype "passive"))
      (node (ref "13") (pin "10") (pinfunction "G_10") (pintype "passive"))
      (node (ref "14") (pin "10") (pinfunction "G_10") (pintype "passive"))
      (node (ref "2") (pin "10") (pinfunction "G_10") (pintype "passive"))
      (node (ref "3") (pin "10") (pinfunction "G_10") (pintype "passive"))
      (node (ref "4") (pin "10") (pinfunction "G_10") (pintype "passive"))
      (node (ref "5") (pin "10") (pinfunction "G_10") (pintype "passive"))
      (node (ref "6") (pin "10") (pinfunction "G_10") (pintype "passive"))
      (node (ref "7") (pin "10") (pinfunction "G_10") (pintype "passive"))
      (node (ref "8") (pin "10") (pinfunction "G_10") (pintype "passive"))
      (node (ref "9") (pin "10") (pinfunction "G_10") (pintype "passive"))
      (node (ref "R2") (pin "2") (pinfunction "2_2") (pintype "passive"))
    )
    (net (code "11") (name "/H1") (class "Default")
      (node (ref "1") (pin "3") (pinfunction "G1_3") (pintype "passive"))
      (node (ref "1") (pin "8") (pinfunction "G2_8") (pintype "passive"))
      (node (ref "Q10") (pin "2") (pinfunction "E_2") (pintype "passive"))
    )
    (net (code "12") (name "/H2") (class "Default")
      (node (ref "2") (pin "3") (pinfunction "G1_3") (pintype "passive"))
      (node (ref "2") (pin "8") (pinfunction "G2_8") (pintype "passive"))
      (node (ref "Q7") (pin "2") (pinfunction "E_2") (pintype "passive"))
    )
    (net (code "13") (name "/M1") (class "Default")
      (node (ref "3") (pin "3") (pinfunction "G1_3") (pintype "passive"))
      (node (ref "3") (pin "8") (pinfunction "G2_8") (pintype "passive"))
      (node (ref "Q5") (pin "2") (pinfunction "E_2") (pintype "passive"))
    )
    (net (code "14") (name "/M2") (class "Default")
      (node (ref "4") (pin "3") (pinfunction "G1_3") (pintype "passive"))
      (node (ref "4") (pin "8") (pinfunction "G2_8") (pintype "passive"))
      (node (ref "Q3") (pin "2") (pinfunction "E_2") (pintype "passive"))
    )
    (net (code "15") (name "/MISO") (class "Default")
      (node (ref "IC1") (pin "7") (pinfunction "(MISO)PB6_7") (pintype "passive"))
      (node (ref "P1") (pin "5") (pinfunction "5_5") (pintype "passive"))
      (node (ref "R7") (pin "1") (pinfunction "1_1") (pintype "passive"))
    )
    (net (code "16") (name "/MM1") (class "Default")
      (node (ref "9") (pin "3") (pinfunction "G1_3") (pintype "passive"))
      (node (ref "9") (pin "8") (pinfunction "G2_8") (pintype "passive"))
      (node (ref "Q8") (pin "2") (pinfunction "E_2") (pintype "passive"))
    )
    (net (code "17") (name "/MM2") (class "Default")
      (node (ref "10") (pin "3") (pinfunction "G1_3") (pintype "passive"))
      (node (ref "10") (pin "8") (pinfunction "G2_8") (pintype "passive"))
      (node (ref "Q9") (pin "2") (pinfunction "E_2") (pintype "passive"))
    )
    (net (code "18") (name "/MOSI") (class "Default")
      (node (ref "IC1") (pin "6") (pinfunction "(MOSI)PB5_6") (pintype "passive"))
      (node (ref "P1") (pin "6") (pinfunction "6_6") (pintype "passive"))
      (node (ref "R11") (pin "1") (pinfunction "1_1") (pintype "passive"))
    )
    (net (code "20") (name "/P") (class "Default")
      (node (ref "1") (pin "5") (pinfunction "DP_5") (pintype "passive"))
      (node (ref "10") (pin "5") (pinfunction "DP_5") (pintype "passive"))
      (node (ref "11") (pin "5") (pinfunction "DP_5") (pintype "passive"))
      (node (ref "12") (pin "5") (pinfunction "DP_5") (pintype "passive"))
      (node (ref "13") (pin "5") (pinfunction "DP_5") (pintype "passive"))
      (node (ref "14") (pin "5") (pinfunction "DP_5") (pintype "passive"))
      (node (ref "2") (pin "5") (pinfunction "DP_5") (pintype "passive"))
      (node (ref "3") (pin "5") (pinfunction "DP_5") (pintype "passive"))
      (node (ref "4") (pin "5") (pinfunction "DP_5") (pintype "passive"))
      (node (ref "5") (pin "5") (pinfunction "DP_5") (pintype "passive"))
      (node (ref "6") (pin "5") (pinfunction "DP_5") (pintype "passive"))
      (node (ref "7") (pin "5") (pinfunction "DP_5") (pintype "passive"))
      (node (ref "8") (pin "5") (pinfunction "DP_5") (pintype "passive"))
      (node (ref "9") (pin "5") (pinfunction "DP_5") (pintype "passive"))
      (node (ref "R1") (pin "2") (pinfunction "2_2") (pintype "passive"))
    )
    (net (code "21") (name "/PC6") (class "Default")
      (node (ref "IC1") (pin "28") (pinfunction "(TOSC1)PC6_28") (pintype "passive"))
      (node (ref "R18") (pin "1") (pinfunction "1_1") (pintype "passive"))
    )
    (net (code "22") (name "/PC7") (class "Default")
      (node (ref "IC1") (pin "29") (pinfunction "(TOSC2)PC7_29") (pintype "passive"))
      (node (ref "R14") (pin "1") (pinfunction "1_1") (pintype "passive"))
    )
    (net (code "23") (name "/PD4") (class "Default")
      (node (ref "IC1") (pin "18") (pinfunction "(OC1B)PD4_18") (pintype "passive"))
      (node (ref "R24") (pin "1") (pinfunction "1_1") (pintype "passive"))
    )
    (net (code "24") (name "/PD5") (class "Default")
      (node (ref "IC1") (pin "19") (pinfunction "(OC1A)PD5_19") (pintype "passive"))
      (node (ref "R22") (pin "1") (pinfunction "1_1") (pintype "passive"))
    )
    (net (code "25") (name "/PD6") (class "Default")
      (node (ref "IC1") (pin "20") (pinfunction "(ICP)PD6_20") (pintype "passive"))
      (node (ref "R20") (pin "1") (pinfunction "1_1") (pintype "passive"))
    )
    (net (code "26") (name "/PD7") (class "Default")
      (node (ref "IC1") (pin "21") (pinfunction "(OC2)PD7_21") (pintype "passive"))
      (node (ref "R19") (pin "1") (pinfunction "1_1") (pintype "passive"))
    )
    (net (code "27") (name "/RST") (class "Default")
      (node (ref "IC1") (pin "9") (pinfunction "RESET_9") (pintype "passive"))
      (node (ref "P1") (pin "3") (pinfunction "3_3") (pintype "passive"))
    )
    (net (code "28") (name "/S1") (class "Default")
      (node (ref "5") (pin "3") (pinfunction "G1_3") (pintype "passive"))
      (node (ref "5") (pin "8") (pinfunction "G2_8") (pintype "passive"))
      (node (ref "Q2") (pin "2") (pinfunction "E_2") (pintype "passive"))
    )
    (net (code "29") (name "/S2") (class "Default")
      (node (ref "6") (pin "3") (pinfunction "G1_3") (pintype "passive"))
      (node (ref "6") (pin "8") (pinfunction "G2_8") (pintype "passive"))
      (node (ref "Q1") (pin "2") (pinfunction "E_2") (pintype "passive"))
    )
    (net (code "30") (name "/SCK") (class "Default")
      (node (ref "IC1") (pin "8") (pinfunction "(SCK)PB7_8") (pintype "passive"))
      (node (ref "P1") (pin "4") (pinfunction "4_4") (pintype "passive"))
      (node (ref "R10") (pin "1") (pinfunction "1_1") (pintype "passive"))
    )
    (net (code "31") (name "/SCL") (class "Default")
      (node (ref "IC1") (pin "22") (pinfunction "(SCL)PC0_22") (pintype "passive"))
      (node (ref "P2") (pin "4") (pinfunction "4_4") (pintype "passive"))
      (node (ref "P3") (pin "4") (pinfunction "4_4") (pintype "passive"))
      (node (ref "R27") (pin "2") (pinfunction "2_2") (pintype "passive"))
    )
    (net (code "32") (name "/SDA") (class "Default")
      (node (ref "IC1") (pin "23") (pinfunction "(SDA)PC1_23") (pintype "passive"))
      (node (ref "P2") (pin "3") (pinfunction "3_3") (pintype "passive"))
      (node (ref "P3") (pin "3") (pinfunction "3_3") (pintype "passive"))
      (node (ref "R28") (pin "2") (pinfunction "2_2") (pintype "passive"))
    )
    (net (code "33") (name "/TMP1") (class "Default")
      (node (ref "7") (pin "3") (pinfunction "G1_3") (pintype "passive"))
      (node (ref "7") (pin "8") (pinfunction "G2_8") (pintype "passive"))
      (node (ref "Q13") (pin "2") (pinfunction "E_2") (pintype "passive"))
    )
    (net (code "34") (name "/TMP2") (class "Default")
      (node (ref "8") (pin "3") (pinfunction "G1_3") (pintype "passive"))
      (node (ref "8") (pin "8") (pinfunction "G2_8") (pintype "passive"))
      (node (ref "Q14") (pin "2") (pinfunction "E_2") (pintype "passive"))
    )
    (net (code "35") (name "/YY1") (class "Default")
      (node (ref "11") (pin "3") (pinfunction "G1_3") (pintype "passive"))
      (node (ref "11") (pin "8") (pinfunction "G2_8") (pintype "passive"))
      (node (ref "Q11") (pin "2") (pinfunction "E_2") (pintype "passive"))
    )
    (net (code "36") (name "/YY2") (class "Default")
      (node (ref "12") (pin "3") (pinfunction "G1_3") (pintype "passive"))
      (node (ref "12") (pin "8") (pinfunction "G2_8") (pintype "passive"))
      (node (ref "Q12") (pin "2") (pinfunction "E_2") (pintype "passive"))
    )
    (net (code "37") (name "GND") (class "Default")
      (node (ref "C1") (pin "1") (pinfunction "1_1") (pintype "passive"))
      (node (ref "C2") (pin "1") (pinfunction "1_1") (pintype "passive"))
      (node (ref "IC1") (pin "11") (pinfunction "GND_11") (pintype "power_in"))
      (node (ref "IC1") (pin "31") (pinfunction "GND_31") (pintype "power_in"))
      (node (ref "P1") (pin "1") (pinfunction "1_1") (pintype "passive"))
      (node (ref "P2") (pin "1") (pinfunction "1_1") (pintype "passive"))
      (node (ref "P3") (pin "1") (pinfunction "1_1") (pintype "passive"))
      (node (ref "S1") (pin "3") (pinfunction "2_3") (pintype "passive"))
      (node (ref "S2") (pin "3") (pinfunction "2_3") (pintype "passive"))
      (node (ref "S3") (pin "3") (pinfunction "2_3") (pintype "passive"))
      (node (ref "S4") (pin "3") (pinfunction "2_3") (pintype "passive"))
    )
    (net (code "38") (name "Net-(D1-PadA)") (class "Default")
      (node (ref "D1") (pin "A") (pinfunction "A_A") (pintype "passive"))
      (node (ref "J1") (pin "1") (pinfunction "1_1") (pintype "passive"))
    )
    (net (code "39") (name "Net-(D2-PadC)") (class "Default")
      (node (ref "D2") (pin "C") (pinfunction "C_C") (pintype "passive"))
      (node (ref "P1") (pin "2") (pinfunction "2_2") (pintype "passive"))
    )
    (net (code "40") (name "Net-(IC1-(ADC0)PA0)") (class "Default")
      (node (ref "IC1") (pin "40") (pinfunction "(ADC0)PA0_40") (pintype "passive"))
      (node (ref "R9") (pin "1") (pinfunction "1_1") (pintype "passive"))
    )
    (net (code "41") (name "Net-(IC1-(ADC1)PA1)") (class "Default")
      (node (ref "IC1") (pin "39") (pinfunction "(ADC1)PA1_39") (pintype "passive"))
      (node (ref "R8") (pin "1") (pinfunction "1_1") (pintype "passive"))
    )
    (net (code "42") (name "Net-(IC1-(ADC2)PA2)") (class "Default")
      (node (ref "IC1") (pin "38") (pinfunction "(ADC2)PA2_38") (pintype "passive"))
      (node (ref "R6") (pin "1") (pinfunction "1_1") (pintype "passive"))
    )
    (net (code "43") (name "Net-(IC1-(ADC3)PA3)") (class "Default")
      (node (ref "IC1") (pin "37") (pinfunction "(ADC3)PA3_37") (pintype "passive"))
      (node (ref "R5") (pin "1") (pinfunction "1_1") (pintype "passive"))
    )
    (net (code "44") (name "Net-(IC1-(ADC4)PA4)") (class "Default")
      (node (ref "IC1") (pin "36") (pinfunction "(ADC4)PA4_36") (pintype "passive"))
      (node (ref "R4") (pin "1") (pinfunction "1_1") (pintype "passive"))
    )
    (net (code "45") (name "Net-(IC1-(ADC5)PA5)") (class "Default")
      (node (ref "IC1") (pin "35") (pinfunction "(ADC5)PA5_35") (pintype "passive"))
      (node (ref "R3") (pin "1") (pinfunction "1_1") (pintype "passive"))
    )
    (net (code "46") (name "Net-(IC1-(ADC6)PA6)") (class "Default")
      (node (ref "IC1") (pin "34") (pinfunction "(ADC6)PA6_34") (pintype "passive"))
      (node (ref "R2") (pin "1") (pinfunction "1_1") (pintype "passive"))
    )
    (net (code "47") (name "Net-(IC1-(ADC7)PA7)") (class "Default")
      (node (ref "IC1") (pin "33") (pinfunction "(ADC7)PA7_33") (pintype "passive"))
      (node (ref "R1") (pin "1") (pinfunction "1_1") (pintype "passive"))
    )
    (net (code "48") (name "Net-(IC1-(AIN0{slash}INT2)PB2)") (class "Default")
      (node (ref "IC1") (pin "3") (pinfunction "(AIN0/INT2)PB2_3") (pintype "passive"))
      (node (ref "R15") (pin "1") (pinfunction "1_1") (pintype "passive"))
    )
    (net (code "49") (name "Net-(IC1-(AIN1{slash}OC0)PB3)") (class "Default")
      (node (ref "IC1") (pin "4") (pinfunction "(AIN1/OC0)PB3_4") (pintype "passive"))
      (node (ref "R13") (pin "1") (pinfunction "1_1") (pintype "passive"))
    )
    (net (code "50") (name "Net-(IC1-(SS)PB4)") (class "Default")
      (node (ref "IC1") (pin "5") (pinfunction "(SS)PB4_5") (pintype "passive"))
      (node (ref "R12") (pin "1") (pinfunction "1_1") (pintype "passive"))
    )
    (net (code "51") (name "Net-(IC1-(T0{slash}XCK)PB0)") (class "Default")
      (node (ref "IC1") (pin "1") (pinfunction "(T0/XCK)PB0_1") (pintype "passive"))
      (node (ref "R17") (pin "1") (pinfunction "1_1") (pintype "passive"))
    )
    (net (code "52") (name "Net-(IC1-(T1)PB1)") (class "Default")
      (node (ref "IC1") (pin "2") (pinfunction "(T1)PB1_2") (pintype "passive"))
      (node (ref "R16") (pin "1") (pinfunction "1_1") (pintype "passive"))
    )
    (net (code "53") (name "Net-(IC1-(TCK)PC2)") (class "Default")
      (node (ref "IC1") (pin "24") (pinfunction "(TCK)PC2_24") (pintype "passive"))
      (node (ref "R21") (pin "1") (pinfunction "1_1") (pintype "passive"))
      (node (ref "S1") (pin "1") (pinfunction "1_1") (pintype "passive"))
    )
    (net (code "54") (name "Net-(IC1-(TDI)PC5)") (class "Default")
      (node (ref "IC1") (pin "27") (pinfunction "(TDI)PC5_27") (pintype "passive"))
      (node (ref "R26") (pin "1") (pinfunction "1_1") (pintype "passive"))
      (node (ref "S4") (pin "1") (pinfunction "1_1") (pintype "passive"))
    )
    (net (code "55") (name "Net-(IC1-(TDO)PC4)") (class "Default")
      (node (ref "IC1") (pin "26") (pinfunction "(TDO)PC4_26") (pintype "passive"))
      (node (ref "R25") (pin "1") (pinfunction "1_1") (pintype "passive"))
      (node (ref "S3") (pin "1") (pinfunction "1_1") (pintype "passive"))
    )
    (net (code "56") (name "Net-(IC1-(TMS)PC3)") (class "Default")
      (node (ref "IC1") (pin "25") (pinfunction "(TMS)PC3_25") (pintype "passive"))
      (node (ref "R23") (pin "1") (pinfunction "1_1") (pintype "passive"))
      (node (ref "S2") (pin "1") (pinfunction "1_1") (pintype "passive"))
    )
    (net (code "57") (name "Net-(IC1-XTAL1)") (class "Default")
      (node (ref "C2") (pin "2") (pinfunction "2_2") (pintype "passive"))
      (node (ref "IC1") (pin "13") (pinfunction "XTAL1_13") (pintype "passive"))
      (node (ref "Y1") (pin "1") (pinfunction "1_1") (pintype "passive"))
    )
    (net (code "58") (name "Net-(IC1-XTAL2)") (class "Default")
      (node (ref "C1") (pin "2") (pinfunction "2_2") (pintype "passive"))
      (node (ref "IC1") (pin "12") (pinfunction "XTAL2_12") (pintype "passive"))
      (node (ref "Y1") (pin "2") (pinfunction "2_2") (pintype "passive"))
    )
    (net (code "59") (name "Net-(J1-SHIELD)") (class "Default")
      (node (ref "J1") (pin "5") (pinfunction "5_5") (pintype "passive"))
      (node (ref "J1") (pin "S") (pinfunction "SHIELD_S") (pintype "passive"))
      (node (ref "U1") (pin "2") (pinfunction "GND_2") (pintype "power_in"))
    )
    (net (code "60") (name "Net-(Q1-B)") (class "Default")
      (node (ref "Q1") (pin "1") (pinfunction "B_1") (pintype "passive"))
      (node (ref "R11") (pin "2") (pinfunction "2_2") (pintype "passive"))
    )
    (net (code "61") (name "Net-(Q2-B)") (class "Default")
      (node (ref "Q2") (pin "1") (pinfunction "B_1") (pintype "passive"))
      (node (ref "R12") (pin "2") (pinfunction "2_2") (pintype "passive"))
    )
    (net (code "62") (name "Net-(Q3-B)") (class "Default")
      (node (ref "Q3") (pin "1") (pinfunction "B_1") (pintype "passive"))
      (node (ref "R13") (pin "2") (pinfunction "2_2") (pintype "passive"))
    )
    (net (code "63") (name "Net-(Q4-B)") (class "Default")
      (node (ref "Q4") (pin "1") (pinfunction "B_1") (pintype "passive"))
      (node (ref "R7") (pin "2") (pinfunction "2_2") (pintype "passive"))
    )
    (net (code "64") (name "Net-(Q5-B)") (class "Default")
      (node (ref "Q5") (pin "1") (pinfunction "B_1") (pintype "passive"))
      (node (ref "R15") (pin "2") (pinfunction "2_2") (pintype "passive"))
    )
    (net (code "65") (name "Net-(Q6-B)") (class "Default")
      (node (ref "Q6") (pin "1") (pinfunction "B_1") (pintype "passive"))
      (node (ref "R10") (pin "2") (pinfunction "2_2") (pintype "passive"))
    )
    (net (code "66") (name "Net-(Q7-B)") (class "Default")
      (node (ref "Q7") (pin "1") (pinfunction "B_1") (pintype "passive"))
      (node (ref "R16") (pin "2") (pinfunction "2_2") (pintype "passive"))
    )
    (net (code "67") (name "Net-(Q8-B)") (class "Default")
      (node (ref "Q8") (pin "1") (pinfunction "B_1") (pintype "passive"))
      (node (ref "R14") (pin "2") (pinfunction "2_2") (pintype "passive"))
    )
    (net (code "68") (name "Net-(Q9-B)") (class "Default")
      (node (ref "Q9") (pin "1") (pinfunction "B_1") (pintype "passive"))
      (node (ref "R18") (pin "2") (pinfunction "2_2") (pintype "passive"))
    )
    (net (code "69") (name "Net-(Q10-B)") (class "Default")
      (node (ref "Q10") (pin "1") (pinfunction "B_1") (pintype "passive"))
      (node (ref "R17") (pin "2") (pinfunction "2_2") (pintype "passive"))
    )
    (net (code "70") (name "Net-(Q11-B)") (class "Default")
      (node (ref "Q11") (pin "1") (pinfunction "B_1") (pintype "passive"))
      (node (ref "R19") (pin "2") (pinfunction "2_2") (pintype "passive"))
    )
    (net (code "71") (name "Net-(Q12-B)") (class "Default")
      (node (ref "Q12") (pin "1") (pinfunction "B_1") (pintype "passive"))
      (node (ref "R20") (pin "2") (pinfunction "2_2") (pintype "passive"))
    )
    (net (code "72") (name "Net-(Q13-B)") (class "Default")
      (node (ref "Q13") (pin "1") (pinfunction "B_1") (pintype "passive"))
      (node (ref "R22") (pin "2") (pinfunction "2_2") (pintype "passive"))
    )
    (net (code "73") (name "Net-(Q14-B)") (class "Default")
      (node (ref "Q14") (pin "1") (pinfunction "B_1") (pintype "passive"))
      (node (ref "R24") (pin "2") (pinfunction "2_2") (pintype "passive"))
    )
    (net (code "74") (name "Net-(U1-IN)") (class "Default")
      (node (ref "D1") (pin "C") (pinfunction "C_C") (pintype "passive"))
      (node (ref "U1") (pin "1") (pinfunction "IN_1") (pintype "power_in"))
    )
    (net (code "75") (name "unconnected-(IC1-(INT0)PD2-Pad16)") (class "Default")
      (node (ref "IC1") (pin "16") (pinfunction "(INT0)PD2_16") (pintype "passive"))
    )
    (net (code "76") (name "unconnected-(IC1-(INT1)PD3-Pad17)") (class "Default")
      (node (ref "IC1") (pin "17") (pinfunction "(INT1)PD3_17") (pintype "passive"))
    )
    (net (code "77") (name "unconnected-(IC1-(RXD)PD0-Pad14)") (class "Default")
      (node (ref "IC1") (pin "14") (pinfunction "(RXD)PD0_14") (pintype "passive"))
    )
    (net (code "78") (name "unconnected-(IC1-(TXD)PD1-Pad15)") (class "Default")
      (node (ref "IC1") (pin "15") (pinfunction "(TXD)PD1_15") (pintype "passive"))
    )
    (net (code "79") (name "unconnected-(J1-Pad2)") (class "Default")
      (node (ref "J1") (pin "2") (pinfunction "2_2") (pintype "passive"))
    )
    (net (code "80") (name "unconnected-(J1-Pad3)") (class "Default")
      (node (ref "J1") (pin "3") (pinfunction "3_3") (pintype "passive"))
    )
    (net (code "81") (name "unconnected-(J1-Pad4)") (class "Default")
      (node (ref "J1") (pin "4") (pinfunction "4_4") (pintype "passive"))
    )
  )
)
